# seguidor_LDR_12.net
KiCad netlist of a schematic drawn in EAGLE
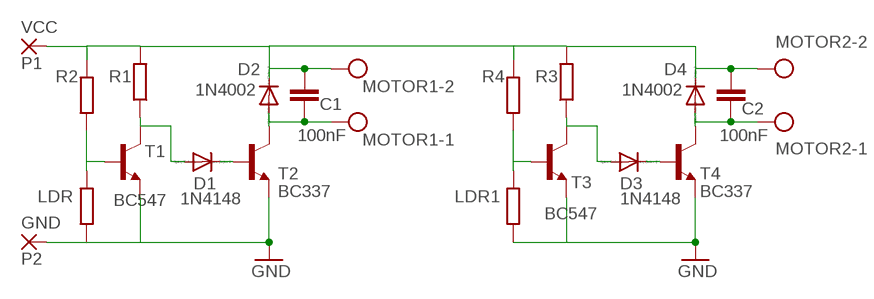
[diagram p0: schematic, sheet 1]

(export (version "E")
  (design (tool "Eeschema 10.0.6"))
  (components
    (comp (ref "C1")
      (value "100nF")
      (footprint "eagle-import:C050-025X075")
      (libsource (lib "eagle-import") (part "C-EU050-025X075"))
    )
    (comp (ref "C2")
      (value "100nF")
      (footprint "eagle-import:C050-025X075")
      (libsource (lib "eagle-import") (part "C-EU050-025X075"))
    )
    (comp (ref "D1")
      (value "1N4148")
      (footprint "eagle-import:DO35-10")
      (libsource (lib "eagle-import") (part "1N4148DO35-10"))
    )
    (comp (ref "D2")
      (value "1N4002")
      (footprint "eagle-import:DO41-10")
      (libsource (lib "eagle-import") (part "1N4004"))
    )
    (comp (ref "D3")
      (value "1N4148")
      (footprint "eagle-import:DO35-10")
      (libsource (lib "eagle-import") (part "1N4148DO35-10"))
    )
    (comp (ref "D4")
      (value "1N4002")
      (footprint "eagle-import:DO41-10")
      (libsource (lib "eagle-import") (part "1N4004"))
    )
    (comp (ref "GND")
      (value "P2")
      (footprint "eagle-import:2,15_1,0")
      (libsource (lib "eagle-import") (part "WIREPAD2,15/1,0"))
    )
    (comp (ref "LDR")
      (value "R-EU_0204/5")
      (footprint "eagle-import:0204_5")
      (libsource (lib "eagle-import") (part "R-EU_0204/5"))
    )
    (comp (ref "LDR1")
      (value "R-EU_0204/5")
      (footprint "eagle-import:0204_5")
      (libsource (lib "eagle-import") (part "R-EU_0204/5"))
    )
    (comp (ref "MOTOR1")
      (value "AK500/2")
      (footprint "eagle-import:AK500_2")
      (libsource (lib "eagle-import") (part "AK500/2"))
    )
    (comp (ref "MOTOR2")
      (value "AK500/2")
      (footprint "eagle-import:AK500_2")
      (libsource (lib "eagle-import") (part "AK500/2"))
    )
    (comp (ref "R1")
      (value "R-EU_0207/10")
      (footprint "eagle-import:0207_10")
      (libsource (lib "eagle-import") (part "R-EU_0207/10"))
    )
    (comp (ref "R2")
      (value "R-EU_0207/10")
      (footprint "eagle-import:0207_10")
      (libsource (lib "eagle-import") (part "R-EU_0207/10"))
    )
    (comp (ref "R3")
      (value "R-EU_0207/10")
      (footprint "eagle-import:0207_10")
      (libsource (lib "eagle-import") (part "R-EU_0207/10"))
    )
    (comp (ref "R4")
      (value "R-EU_0207/10")
      (footprint "eagle-import:0207_10")
      (libsource (lib "eagle-import") (part "R-EU_0207/10"))
    )
    (comp (ref "T1")
      (value "BC547")
      (footprint "eagle-import:TO92-CBE")
      (libsource (lib "eagle-import") (part "-NPN-TO92-CBEBC337-16"))
    )
    (comp (ref "T2")
      (value "BC337")
      (footprint "eagle-import:TO92-CBE")
      (libsource (lib "eagle-import") (part "-NPN-TO92-CBEBC337-16"))
    )
    (comp (ref "T3")
      (value "BC547")
      (footprint "eagle-import:TO92-CBE")
      (libsource (lib "eagle-import") (part "-NPN-TO92-CBEBC337-16"))
    )
    (comp (ref "T4")
      (value "BC337")
      (footprint "eagle-import:TO92-CBE")
      (libsource (lib "eagle-import") (part "-NPN-TO92-CBEBC337-16"))
    )
    (comp (ref "VCC")
      (value "P1")
      (footprint "eagle-import:2,15_1,0")
      (libsource (lib "eagle-import") (part "WIREPAD2,15/1,0"))
    )
  )
  (nets
    (net (code "1") (name "GND") (class "Default")
      (node (ref "GND") (pin "1") (pinfunction "P_1") (pintype "passive"))
      (node (ref "LDR") (pin "1") (pinfunction "1_1") (pintype "passive"))
      (node (ref "LDR1") (pin "1") (pinfunction "1_1") (pintype "passive"))
      (node (ref "T1") (pin "E") (pinfunction "E_E") (pintype "passive"))
      (node (ref "T2") (pin "E") (pinfunction "E_E") (pintype "passive"))
      (node (ref "T3") (pin "E") (pinfunction "E_E") (pintype "passive"))
      (node (ref "T4") (pin "E") (pinfunction "E_E") (pintype "passive"))
    )
    (net (code "2") (name "Net-(D1-PadA)") (class "Default")
      (node (ref "D1") (pin "A") (pinfunction "A_A") (pintype "passive"))
      (node (ref "R1") (pin "1") (pinfunction "1_1") (pintype "passive"))
      (node (ref "T1") (pin "C") (pinfunction "C_C") (pintype "passive"))
    )
    (net (code "3") (name "Net-(D1-PadC)") (class "Default")
      (node (ref "D1") (pin "C") (pinfunction "C_C") (pintype "passive"))
      (node (ref "T2") (pin "B") (pinfunction "B_B") (pintype "passive"))
    )
    (net (code "4") (name "Net-(D3-PadA)") (class "Default")
      (node (ref "D3") (pin "A") (pinfunction "A_A") (pintype "passive"))
      (node (ref "R3") (pin "1") (pinfunction "1_1") (pintype "passive"))
      (node (ref "T3") (pin "C") (pinfunction "C_C") (pintype "passive"))
    )
    (net (code "5") (name "Net-(D3-PadC)") (class "Default")
      (node (ref "D3") (pin "C") (pinfunction "C_C") (pintype "passive"))
      (node (ref "T4") (pin "B") (pinfunction "B_B") (pintype "passive"))
    )
    (net (code "6") (name "Net-(LDR-Pad2)") (class "Default")
      (node (ref "LDR") (pin "2") (pinfunction "2_2") (pintype "passive"))
      (node (ref "R2") (pin "1") (pinfunction "1_1") (pintype "passive"))
      (node (ref "T1") (pin "B") (pinfunction "B_B") (pintype "passive"))
    )
    (net (code "7") (name "Net-(LDR1-Pad2)") (class "Default")
      (node (ref "LDR1") (pin "2") (pinfunction "2_2") (pintype "passive"))
      (node (ref "R4") (pin "1") (pinfunction "1_1") (pintype "passive"))
      (node (ref "T3") (pin "B") (pinfunction "B_B") (pintype "passive"))
    )
    (net (code "8") (name "Net-(MOTOR1A-KL)") (class "Default")
      (node (ref "C1") (pin "2") (pinfunction "2_2") (pintype "passive"))
      (node (ref "D2") (pin "A") (pinfunction "A_A") (pintype "passive"))
      (node (ref "MOTOR1") (pin "1") (pinfunction "KL_1") (pintype "passive"))
      (node (ref "T2") (pin "C") (pinfunction "C_C") (pintype "passive"))
    )
    (net (code "9") (name "Net-(MOTOR1B-KL)") (class "Default")
      (node (ref "C1") (pin "1") (pinfunction "1_1") (pintype "passive"))
      (node (ref "C2") (pin "1") (pinfunction "1_1") (pintype "passive"))
      (node (ref "D2") (pin "C") (pinfunction "C_C") (pintype "passive"))
      (node (ref "D4") (pin "C") (pinfunction "C_C") (pintype "passive"))
      (node (ref "MOTOR1") (pin "2") (pinfunction "KL_2") (pintype "passive"))
      (node (ref "MOTOR2") (pin "2") (pinfunction "KL_2") (pintype "passive"))
      (node (ref "R1") (pin "2") (pinfunction "2_2") (pintype "passive"))
      (node (ref "R2") (pin "2") (pinfunction "2_2") (pintype "passive"))
      (node (ref "R3") (pin "2") (pinfunction "2_2") (pintype "passive"))
      (node (ref "R4") (pin "2") (pinfunction "2_2") (pintype "passive"))
      (node (ref "VCC") (pin "1") (pinfunction "P_1") (pintype "passive"))
    )
    (net (code "10") (name "Net-(MOTOR2A-KL)") (class "Default")
      (node (ref "C2") (pin "2") (pinfunction "2_2") (pintype "passive"))
      (node (ref "D4") (pin "A") (pinfunction "A_A") (pintype "passive"))
      (node (ref "MOTOR2") (pin "1") (pinfunction "KL_1") (pintype "passive"))
      (node (ref "T4") (pin "C") (pinfunction "C_C") (pintype "passive"))
    )
  )
)
